# openmv2.net
KiCad netlist of a schematic drawn in EAGLE
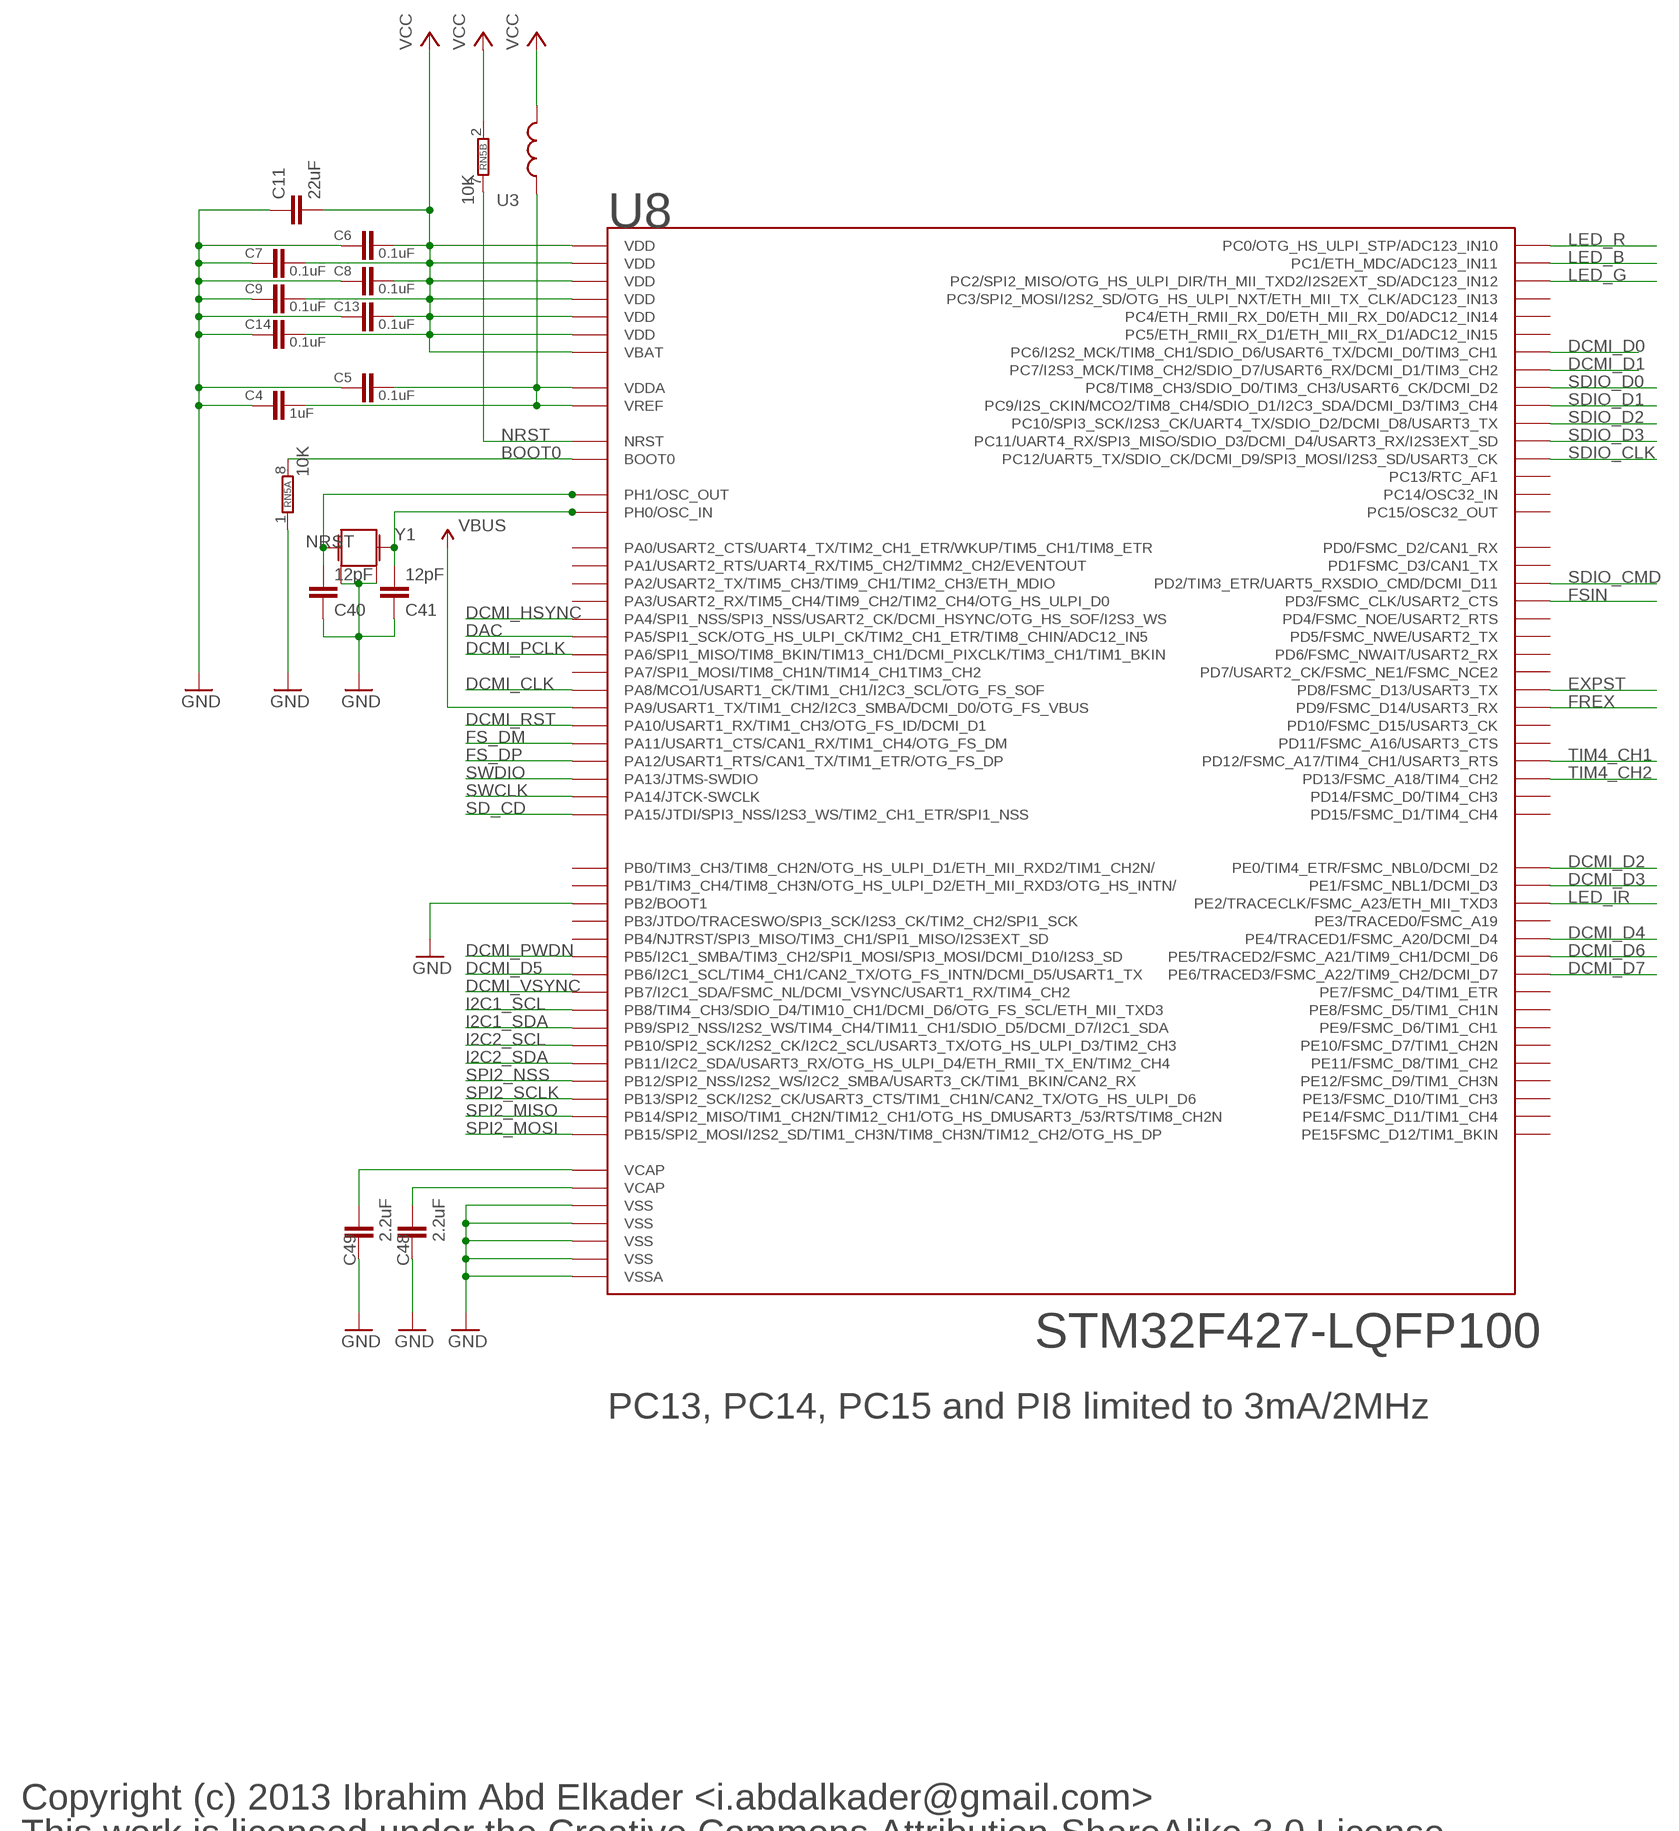
[diagram p0: schematic, sheet 1, part 1 of 2]
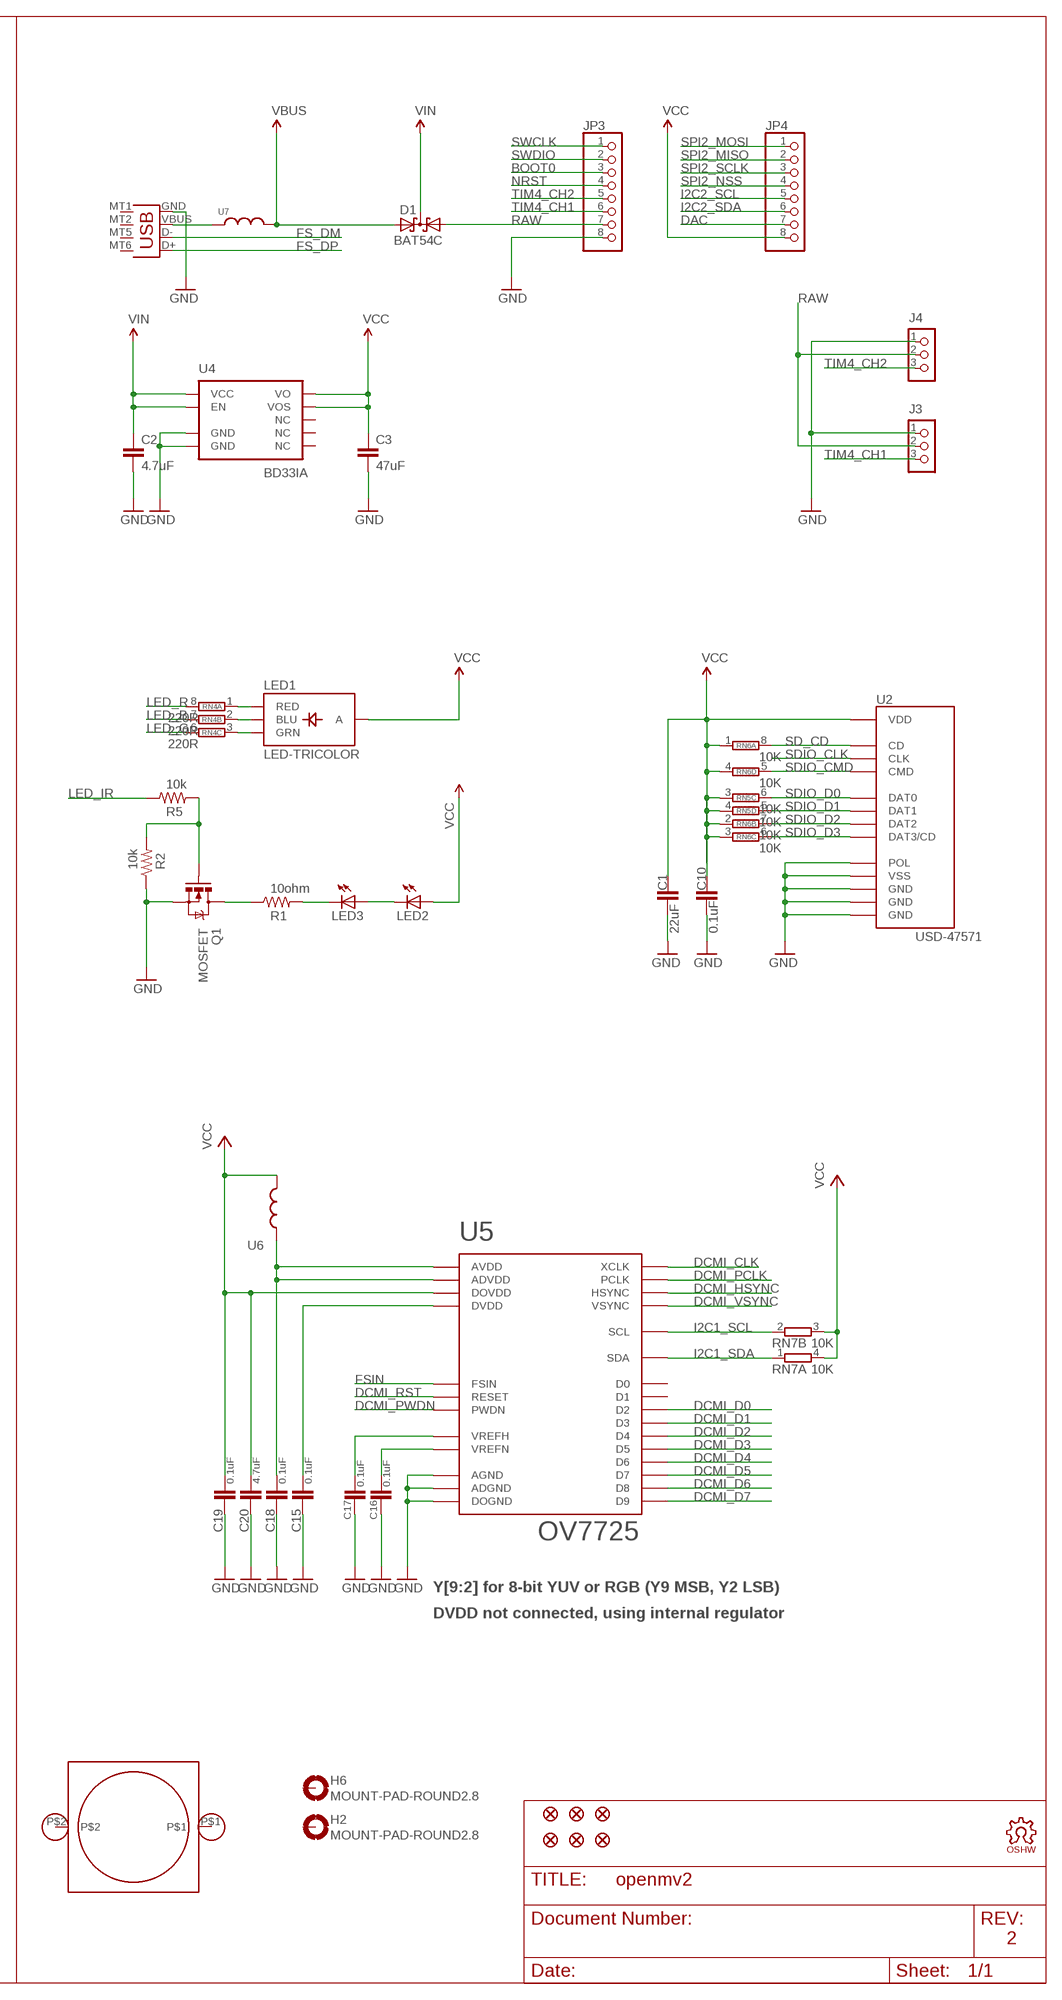
[diagram p1: schematic, sheet 1, part 2 of 2]

(export (version "E")
  (design (tool "Eeschema 10.0.6"))
  (components
    (comp (ref "C1")
      (value "22uF")
      (footprint "eagle-import:0805")
      (libsource (lib "eagle-import") (part "CAP0805"))
    )
    (comp (ref "C2")
      (value "4.7uF")
      (footprint "eagle-import:0603-CAP")
      (libsource (lib "eagle-import") (part "CAP0603-CAP"))
    )
    (comp (ref "C3")
      (value "47uF")
      (footprint "eagle-import:1206")
      (libsource (lib "eagle-import") (part "CAP1206"))
    )
    (comp (ref "C4")
      (value "1uF")
      (footprint "eagle-import:0603-CAP")
      (libsource (lib "eagle-import") (part "CAP0603-CAP"))
    )
    (comp (ref "C5")
      (value "0.1uF")
      (footprint "eagle-import:0603-CAP")
      (libsource (lib "eagle-import") (part "CAP0603-CAP"))
    )
    (comp (ref "C6")
      (value "0.1uF")
      (footprint "eagle-import:0603-CAP")
      (libsource (lib "eagle-import") (part "CAP0603-CAP"))
    )
    (comp (ref "C7")
      (value "0.1uF")
      (footprint "eagle-import:0603-CAP")
      (libsource (lib "eagle-import") (part "CAP0603-CAP"))
    )
    (comp (ref "C8")
      (value "0.1uF")
      (footprint "eagle-import:0603-CAP")
      (libsource (lib "eagle-import") (part "CAP0603-CAP"))
    )
    (comp (ref "C9")
      (value "0.1uF")
      (footprint "eagle-import:0603-CAP")
      (libsource (lib "eagle-import") (part "CAP0603-CAP"))
    )
    (comp (ref "C10")
      (value "0.1uF")
      (footprint "eagle-import:0603-CAP")
      (libsource (lib "eagle-import") (part "CAP0603-CAP"))
    )
    (comp (ref "C11")
      (value "22uF")
      (footprint "eagle-import:0805")
      (libsource (lib "eagle-import") (part "CAP0805"))
    )
    (comp (ref "C13")
      (value "0.1uF")
      (footprint "eagle-import:0603-CAP")
      (libsource (lib "eagle-import") (part "CAP0603-CAP"))
    )
    (comp (ref "C14")
      (value "0.1uF")
      (footprint "eagle-import:0603-CAP")
      (libsource (lib "eagle-import") (part "CAP0603-CAP"))
    )
    (comp (ref "C15")
      (value "0.1uF")
      (footprint "eagle-import:0603-CAP")
      (libsource (lib "eagle-import") (part "CAP0603-CAP"))
    )
    (comp (ref "C16")
      (value "0.1uF")
      (footprint "eagle-import:0603-CAP")
      (libsource (lib "eagle-import") (part "CAP0603-CAP"))
    )
    (comp (ref "C17")
      (value "0.1uF")
      (footprint "eagle-import:0603-CAP")
      (libsource (lib "eagle-import") (part "CAP0603-CAP"))
    )
    (comp (ref "C18")
      (value "0.1uF")
      (footprint "eagle-import:0603-CAP")
      (libsource (lib "eagle-import") (part "CAP0603-CAP"))
    )
    (comp (ref "C19")
      (value "0.1uF")
      (footprint "eagle-import:0603-CAP")
      (libsource (lib "eagle-import") (part "CAP0603-CAP"))
    )
    (comp (ref "C20")
      (value "4.7uF")
      (footprint "eagle-import:0603-CAP")
      (libsource (lib "eagle-import") (part "CAP0603-CAP"))
    )
    (comp (ref "C40")
      (value "12pF")
      (footprint "eagle-import:0603-CAP")
      (libsource (lib "eagle-import") (part "CAP0603-CAP"))
    )
    (comp (ref "C41")
      (value "12pF")
      (footprint "eagle-import:0603-CAP")
      (libsource (lib "eagle-import") (part "CAP0603-CAP"))
    )
    (comp (ref "C48")
      (value "2.2uF")
      (footprint "eagle-import:0603-CAP")
      (libsource (lib "eagle-import") (part "CAP0603-CAP"))
    )
    (comp (ref "C49")
      (value "2.2uF")
      (footprint "eagle-import:0603-CAP")
      (libsource (lib "eagle-import") (part "CAP0603-CAP"))
    )
    (comp (ref "D1")
      (value "BAT54C")
      (footprint "eagle-import:SOT23")
      (libsource (lib "eagle-import") (part "BAT54C"))
    )
    (comp (ref "H2")
      (value "MOUNT-PAD-ROUND2.8")
      (footprint "eagle-import:2,8-PAD")
      (libsource (lib "eagle-import") (part "MOUNT-PAD-ROUND2.8"))
    )
    (comp (ref "H6")
      (value "MOUNT-PAD-ROUND2.8")
      (footprint "eagle-import:2,8-PAD")
      (libsource (lib "eagle-import") (part "MOUNT-PAD-ROUND2.8"))
    )
    (comp (ref "J3")
      (value "CON_HEADER_1X03")
      (footprint "eagle-import:M1X3_SMD")
      (libsource (lib "eagle-import") (part "CON_HEADER_1X03"))
    )
    (comp (ref "J4")
      (value "CON_HEADER_1X03")
      (footprint "eagle-import:M1X3_SMD")
      (libsource (lib "eagle-import") (part "CON_HEADER_1X03"))
    )
    (comp (ref "JP1")
      (value "FIDUCIAL1X2")
      (footprint "eagle-import:FIDUCIAL-1X2")
      (libsource (lib "eagle-import") (part "FIDUCIAL1X2"))
    )
    (comp (ref "JP2")
      (value "FIDUCIAL1X2")
      (footprint "eagle-import:FIDUCIAL-1X2")
      (libsource (lib "eagle-import") (part "FIDUCIAL1X2"))
    )
    (comp (ref "JP3")
      (value "PINHD-1X8")
      (footprint "eagle-import:1X08")
      (libsource (lib "eagle-import") (part "PINHD-1X8"))
    )
    (comp (ref "JP4")
      (value "PINHD-1X8")
      (footprint "eagle-import:1X08")
      (libsource (lib "eagle-import") (part "PINHD-1X8"))
    )
    (comp (ref "JP5")
      (value "FIDUCIAL1X2")
      (footprint "eagle-import:FIDUCIAL-1X2")
      (libsource (lib "eagle-import") (part "FIDUCIAL1X2"))
    )
    (comp (ref "JP6")
      (value "FIDUCIAL1X2")
      (footprint "eagle-import:FIDUCIAL-1X2")
      (libsource (lib "eagle-import") (part "FIDUCIAL1X2"))
    )
    (comp (ref "JP7")
      (value "FIDUCIAL1X2")
      (footprint "eagle-import:FIDUCIAL-1X2")
      (libsource (lib "eagle-import") (part "FIDUCIAL1X2"))
    )
    (comp (ref "JP8")
      (value "FIDUCIAL1X2")
      (footprint "eagle-import:FIDUCIAL-1X2")
      (libsource (lib "eagle-import") (part "FIDUCIAL1X2"))
    )
    (comp (ref "LED1")
      (value "LED-TRICOLOR")
      (footprint "eagle-import:LED-TRICOLOR-SMD")
      (libsource (lib "eagle-import") (part "LED-TRICOLOR"))
    )
    (comp (ref "LED2")
      (value "LED3MM")
      (footprint "eagle-import:LED3MM")
      (libsource (lib "eagle-import") (part "LED3MM"))
    )
    (comp (ref "LED3")
      (value "LED3MM")
      (footprint "eagle-import:LED3MM")
      (libsource (lib "eagle-import") (part "LED3MM"))
    )
    (comp (ref "LOGO1")
      (value "OSHW_LOGO_FILLX0150-NT")
      (footprint "eagle-import:OSHW_FILLX150_NOTEXT")
      (libsource (lib "eagle-import") (part "OSHW_LOGO_FILLX0150-NT"))
    )
    (comp (ref "Q1")
      (value "MOSFET")
      (footprint "eagle-import:SOT23-3")
      (libsource (lib "eagle-import") (part "MOSFET-NCHANNELSMD"))
    )
    (comp (ref "R1")
      (value "10ohm")
      (footprint "eagle-import:0603-RES")
      (libsource (lib "eagle-import") (part "RESISTOR0603-RES"))
    )
    (comp (ref "R2")
      (value "10k")
      (footprint "eagle-import:0603-RES")
      (libsource (lib "eagle-import") (part "RESISTOR0603-RES"))
    )
    (comp (ref "R5")
      (value "10k")
      (footprint "eagle-import:0603-RES")
      (libsource (lib "eagle-import") (part "RESISTOR0603-RES"))
    )
    (comp (ref "RN4")
      (value "220R")
      (footprint "eagle-import:EXBV8V")
      (fields (field (name "OC_FARNELL") "unknown") (field (name "OC_NEWARK") "unknown"))
      (libsource (lib "eagle-import") (part "4R-NEXBV8V"))
    )
    (comp (ref "RN5")
      (value "10K")
      (footprint "eagle-import:EXBV8V")
      (fields (field (name "OC_FARNELL") "unknown") (field (name "OC_NEWARK") "unknown"))
      (libsource (lib "eagle-import") (part "4R-NEXBV8V"))
    )
    (comp (ref "RN6")
      (value "10K")
      (footprint "eagle-import:EXBV8V")
      (fields (field (name "OC_FARNELL") "unknown") (field (name "OC_NEWARK") "unknown"))
      (libsource (lib "eagle-import") (part "4R-NEXBV8V"))
    )
    (comp (ref "RN7")
      (value "10K")
      (footprint "eagle-import:EXBV4V")
      (libsource (lib "eagle-import") (part "2R-NEXBV4V"))
    )
    (comp (ref "U1")
      (value "LENSMOUNT20MM")
      (footprint "eagle-import:LENSMOUNT-20MM")
      (libsource (lib "eagle-import") (part "LENSMOUNT20MM"))
    )
    (comp (ref "U2")
      (value "USD-47571")
      (footprint "eagle-import:USD-47571")
      (libsource (lib "eagle-import") (part "USD-47571"))
    )
    (comp (ref "U3")
      (value "INDUCTOR0603")
      (footprint "eagle-import:0603")
      (libsource (lib "eagle-import") (part "INDUCTOR0603"))
    )
    (comp (ref "U4")
      (value "BD33IA")
      (footprint "eagle-import:HTSOP-J8")
      (libsource (lib "eagle-import") (part "BD33IA"))
    )
    (comp (ref "U5")
      (value "OV7725")
      (footprint "eagle-import:CSP2-28")
      (libsource (lib "eagle-import") (part "OV7725"))
    )
    (comp (ref "U6")
      (value "INDUCTOR0603")
      (footprint "eagle-import:0603")
      (libsource (lib "eagle-import") (part "INDUCTOR0603"))
    )
    (comp (ref "U7")
      (value "INDUCTOR0603")
      (footprint "eagle-import:0603")
      (libsource (lib "eagle-import") (part "INDUCTOR0603"))
    )
    (comp (ref "U8")
      (value "STM32F427-LQFP100")
      (footprint "eagle-import:LQFP100")
      (libsource (lib "eagle-import") (part "STM32F407LQFP100"))
    )
    (comp (ref "X2")
      (value "USB-MICROB")
      (footprint "eagle-import:USB-MICROB")
      (libsource (lib "eagle-import") (part "USB-MICROB"))
    )
    (comp (ref "Y1")
      (value "CRYSTAL2.5X2.0")
      (footprint "eagle-import:CRYSTAL-2.5X2.0")
      (libsource (lib "eagle-import") (part "CRYSTAL2.5X2.0"))
    )
  )
  (nets
    (net (code "1") (name "/BOOT0") (class "Default")
      (node (ref "JP3") (pin "3") (pinfunction "3_3") (pintype "passive"))
      (node (ref "RN5") (pin "8") (pinfunction "2_8") (pintype "passive"))
      (node (ref "U8") (pin "94") (pinfunction "BOOT0_94") (pintype "bidirectional"))
    )
    (net (code "2") (name "/DAC") (class "Default")
      (node (ref "JP4") (pin "7") (pinfunction "7_7") (pintype "passive"))
      (node (ref "U8") (pin "30") (pinfunction "PA5/SPI1_SCK/OTG_HS_ULPI_CK/TIM2_CH1_ETR/TIM8_CHIN/ADC12_IN5_30") (pintype "bidirectional"))
    )
    (net (code "3") (name "/DCMI_CLK") (class "Default")
      (node (ref "U5") (pin "F3") (pinfunction "XCLK_F3") (pintype "bidirectional"))
      (node (ref "U8") (pin "67") (pinfunction "PA8/MCO1/USART1_CK/TIM1_CH1/I2C3_SCL/OTG_FS_SOF_67") (pintype "bidirectional"))
    )
    (net (code "4") (name "/DCMI_D0") (class "Default")
      (node (ref "U5") (pin "F5") (pinfunction "D2_F5") (pintype "bidirectional"))
      (node (ref "U8") (pin "63") (pinfunction "PC6/I2S2_MCK/TIM8_CH1/SDIO_D6/USART6_TX/DCMI_D0/TIM3_CH1_63") (pintype "bidirectional"))
    )
    (net (code "5") (name "/DCMI_D1") (class "Default")
      (node (ref "U5") (pin "F2") (pinfunction "D3_F2") (pintype "bidirectional"))
      (node (ref "U8") (pin "64") (pinfunction "PC7/I2S3_MCK/TIM8_CH2/SDIO_D7/USART6_RX/DCMI_D1/TIM3_CH2_64") (pintype "bidirectional"))
    )
    (net (code "6") (name "/DCMI_D2") (class "Default")
      (node (ref "U5") (pin "D6") (pinfunction "D4_D6") (pintype "bidirectional"))
      (node (ref "U8") (pin "97") (pinfunction "PE0/TIM4_ETR/FSMC_NBL0/DCMI_D2_97") (pintype "bidirectional"))
    )
    (net (code "7") (name "/DCMI_D3") (class "Default")
      (node (ref "U5") (pin "D1") (pinfunction "D5_D1") (pintype "bidirectional"))
      (node (ref "U8") (pin "98") (pinfunction "PE1/FSMC_NBL1/DCMI_D3_98") (pintype "bidirectional"))
    )
    (net (code "8") (name "/DCMI_D4") (class "Default")
      (node (ref "U5") (pin "E6") (pinfunction "D6_E6") (pintype "bidirectional"))
      (node (ref "U8") (pin "3") (pinfunction "PE4/TRACED1/FSMC_A20/DCMI_D4_3") (pintype "bidirectional"))
    )
    (net (code "9") (name "/DCMI_D5") (class "Default")
      (node (ref "U5") (pin "E1") (pinfunction "D7_E1") (pintype "bidirectional"))
      (node (ref "U8") (pin "92") (pinfunction "PB6/I2C1_SCL/TIM4_CH1/CAN2_TX/OTG_FS_INTN/DCMI_D5/USART1_TX_92") (pintype "bidirectional"))
    )
    (net (code "10") (name "/DCMI_D6") (class "Default")
      (node (ref "U5") (pin "F6") (pinfunction "D8_F6") (pintype "bidirectional"))
      (node (ref "U8") (pin "4") (pinfunction "PE5/TRACED2/FSMC_A21/TIM9_CH1/DCMI_D6_4") (pintype "bidirectional"))
    )
    (net (code "11") (name "/DCMI_D7") (class "Default")
      (node (ref "U5") (pin "F1") (pinfunction "D9_F1") (pintype "bidirectional"))
      (node (ref "U8") (pin "5") (pinfunction "PE6/TRACED3/FSMC_A22/TIM9_CH2/DCMI_D7_5") (pintype "bidirectional"))
    )
    (net (code "12") (name "/DCMI_HSYNC") (class "Default")
      (node (ref "U5") (pin "B6") (pinfunction "HSYNC_B6") (pintype "bidirectional"))
      (node (ref "U8") (pin "29") (pinfunction "PA4/SPI1_NSS/SPI3_NSS/USART2_CK/DCMI_HSYNC/OTG_HS_SOF/I2S3_WS_29") (pintype "bidirectional"))
    )
    (net (code "13") (name "/DCMI_PCLK") (class "Default")
      (node (ref "U5") (pin "E4") (pinfunction "PCLK_E4") (pintype "bidirectional"))
      (node (ref "U8") (pin "31") (pinfunction "PA6/SPI1_MISO/TIM8_BKIN/TIM13_CH1/DCMI_PIXCLK/TIM3_CH1/TIM1_BKIN_31") (pintype "bidirectional"))
    )
    (net (code "14") (name "/DCMI_PWDN") (class "Default")
      (node (ref "U5") (pin "C1") (pinfunction "PWDN_C1") (pintype "bidirectional"))
      (node (ref "U8") (pin "91") (pinfunction "PB5/I2C1_SMBA/TIM3_CH2/SPI1_MOSI/SPI3_MOSI/DCMI_D10/I2S3_SD_91") (pintype "bidirectional"))
    )
    (net (code "15") (name "/DCMI_RST") (class "Default")
      (node (ref "U5") (pin "A2") (pinfunction "RESET_A2") (pintype "bidirectional"))
      (node (ref "U8") (pin "69") (pinfunction "PA10/USART1_RX/TIM1_CH3/OTG_FS_ID/DCMI_D1_69") (pintype "bidirectional"))
    )
    (net (code "16") (name "/DCMI_VSYNC") (class "Default")
      (node (ref "U5") (pin "C6") (pinfunction "VSYNC_C6") (pintype "bidirectional"))
      (node (ref "U8") (pin "93") (pinfunction "PB7/I2C1_SDA/FSMC_NL/DCMI_VSYNC/USART1_RX/TIM4_CH2_93") (pintype "bidirectional"))
    )
    (net (code "17") (name "/EXPST") (class "Default")
      (node (ref "U8") (pin "55") (pinfunction "PD8/FSMC_D13/USART3_TX_55") (pintype "bidirectional"))
    )
    (net (code "18") (name "/FREX") (class "Default")
      (node (ref "U8") (pin "56") (pinfunction "PD9/FSMC_D14/USART3_RX_56") (pintype "bidirectional"))
    )
    (net (code "19") (name "/FSIN") (class "Default")
      (node (ref "U5") (pin "A4") (pinfunction "FSIN_A4") (pintype "input"))
      (node (ref "U8") (pin "84") (pinfunction "PD3/FSMC_CLK/USART2_CTS_84") (pintype "bidirectional"))
    )
    (net (code "20") (name "/FS_DM") (class "Default")
      (node (ref "U8") (pin "70") (pinfunction "PA11/USART1_CTS/CAN1_RX/TIM1_CH4/OTG_FS_DM_70") (pintype "bidirectional"))
      (node (ref "X2") (pin "D-") (pinfunction "D-_D-") (pintype "bidirectional"))
    )
    (net (code "21") (name "/FS_DP") (class "Default")
      (node (ref "U8") (pin "71") (pinfunction "PA12/USART1_RTS/CAN1_TX/TIM1_ETR/OTG_FS_DP_71") (pintype "bidirectional"))
      (node (ref "X2") (pin "D+") (pinfunction "D+_D+") (pintype "bidirectional"))
    )
    (net (code "22") (name "/I2C1_SCL") (class "Default")
      (node (ref "RN7") (pin "2") (pinfunction "1_2") (pintype "passive"))
      (node (ref "U5") (pin "A5") (pinfunction "SCL_A5") (pintype "bidirectional"))
      (node (ref "U8") (pin "95") (pinfunction "PB8/TIM4_CH3/SDIO_D4/TIM10_CH1/DCMI_D6/OTG_FS_SCL/ETH_MII_TXD3_95") (pintype "bidirectional"))
    )
    (net (code "23") (name "/I2C1_SDA") (class "Default")
      (node (ref "RN7") (pin "1") (pinfunction "1_1") (pintype "passive"))
      (node (ref "U5") (pin "B5") (pinfunction "SDA_B5") (pintype "bidirectional"))
      (node (ref "U8") (pin "96") (pinfunction "PB9/SPI2_NSS/I2S2_WS/TIM4_CH4/TIM11_CH1/SDIO_D5/DCMI_D7/I2C1_SDA_96") (pintype "bidirectional"))
    )
    (net (code "24") (name "/I2C2_SCL") (class "Default")
      (node (ref "JP4") (pin "5") (pinfunction "5_5") (pintype "passive"))
      (node (ref "U8") (pin "47") (pinfunction "PB10/SPI2_SCK/I2S2_CK/I2C2_SCL/USART3_TX/OTG_HS_ULPI_D3/TIM2_CH3_47") (pintype "bidirectional"))
    )
    (net (code "25") (name "/I2C2_SDA") (class "Default")
      (node (ref "JP4") (pin "6") (pinfunction "6_6") (pintype "passive"))
      (node (ref "U8") (pin "48") (pinfunction "PB11/I2C2_SDA/USART3_RX/OTG_HS_ULPI_D4/ETH_RMII_TX_EN/TIM2_CH4_48") (pintype "bidirectional"))
    )
    (net (code "26") (name "/LED_B") (class "Default")
      (node (ref "RN4") (pin "7") (pinfunction "2_7") (pintype "passive"))
      (node (ref "U8") (pin "16") (pinfunction "PC1/ETH_MDC/ADC123_IN11_16") (pintype "bidirectional"))
    )
    (net (code "27") (name "/LED_G") (class "Default")
      (node (ref "RN4") (pin "6") (pinfunction "2_6") (pintype "passive"))
      (node (ref "U8") (pin "17") (pinfunction "PC2/SPI2_MISO/OTG_HS_ULPI_DIR/TH_MII_TXD2/I2S2EXT_SD/ADC123_IN12_17") (pintype "bidirectional"))
    )
    (net (code "28") (name "/LED_IR") (class "Default")
      (node (ref "R5") (pin "1") (pinfunction "1_1") (pintype "passive"))
      (node (ref "U8") (pin "1") (pinfunction "PE2/TRACECLK/FSMC_A23/ETH_MII_TXD3_1") (pintype "bidirectional"))
    )
    (net (code "29") (name "/LED_R") (class "Default")
      (node (ref "RN4") (pin "8") (pinfunction "2_8") (pintype "passive"))
      (node (ref "U8") (pin "15") (pinfunction "PC0/OTG_HS_ULPI_STP/ADC123_IN10_15") (pintype "bidirectional"))
    )
    (net (code "30") (name "/NRST") (class "Default")
      (node (ref "JP3") (pin "4") (pinfunction "4_4") (pintype "passive"))
      (node (ref "RN5") (pin "7") (pinfunction "2_7") (pintype "passive"))
      (node (ref "U8") (pin "14") (pinfunction "NRST_14") (pintype "bidirectional"))
    )
    (net (code "31") (name "/P$1") (class "Default")
      (node (ref "U1") (pin "P$1") (pinfunction "P$1_P$1") (pintype "power_in"))
    )
    (net (code "32") (name "/P$2") (class "Default")
      (node (ref "U1") (pin "P$2") (pinfunction "P$2_P$2") (pintype "power_in"))
    )
    (net (code "33") (name "/RAW") (class "Default")
      (node (ref "D1") (pin "1") (pinfunction "A1_1") (pintype "passive"))
      (node (ref "J3") (pin "2") (pinfunction "2_2") (pintype "bidirectional"))
      (node (ref "J4") (pin "2") (pinfunction "2_2") (pintype "bidirectional"))
      (node (ref "JP3") (pin "7") (pinfunction "7_7") (pintype "passive"))
    )
    (net (code "34") (name "/SDIO_CLK") (class "Default")
      (node (ref "U2") (pin "P$5") (pinfunction "CLK_P$5") (pintype "bidirectional"))
      (node (ref "U8") (pin "80") (pinfunction "PC12/UART5_TX/SDIO_CK/DCMI_D9/SPI3_MOSI/I2S3_SD/USART3_CK_80") (pintype "bidirectional"))
    )
    (net (code "35") (name "/SDIO_CMD") (class "Default")
      (node (ref "RN6") (pin "5") (pinfunction "2_5") (pintype "passive"))
      (node (ref "U2") (pin "P$3") (pinfunction "CMD_P$3") (pintype "bidirectional"))
      (node (ref "U8") (pin "83") (pinfunction "PD2/TIM3_ETR/UART5_RXSDIO_CMD/DCMI_D11_83") (pintype "bidirectional"))
    )
    (net (code "36") (name "/SDIO_D0") (class "Default")
      (node (ref "RN5") (pin "6") (pinfunction "2_6") (pintype "passive"))
      (node (ref "U2") (pin "P$7") (pinfunction "DAT0_P$7") (pintype "bidirectional"))
      (node (ref "U8") (pin "65") (pinfunction "PC8/TIM8_CH3/SDIO_D0/TIM3_CH3/USART6_CK/DCMI_D2_65") (pintype "bidirectional"))
    )
    (net (code "37") (name "/SDIO_D1") (class "Default")
      (node (ref "RN5") (pin "5") (pinfunction "2_5") (pintype "passive"))
      (node (ref "U2") (pin "P$8") (pinfunction "DAT1_P$8") (pintype "bidirectional"))
      (node (ref "U8") (pin "66") (pinfunction "PC9/I2S_CKIN/MCO2/TIM8_CH4/SDIO_D1/I2C3_SDA/DCMI_D3/TIM3_CH4_66") (pintype "bidirectional"))
    )
    (net (code "38") (name "/SDIO_D2") (class "Default")
      (node (ref "RN6") (pin "7") (pinfunction "2_7") (pintype "passive"))
      (node (ref "U2") (pin "P$1") (pinfunction "DAT2_P$1") (pintype "bidirectional"))
      (node (ref "U8") (pin "78") (pinfunction "PC10/SPI3_SCK/I2S3_CK/UART4_TX/SDIO_D2/DCMI_D8/USART3_TX_78") (pintype "bidirectional"))
    )
    (net (code "39") (name "/SDIO_D3") (class "Default")
      (node (ref "RN6") (pin "6") (pinfunction "2_6") (pintype "passive"))
      (node (ref "U2") (pin "P$2") (pinfunction "DAT3/CD_P$2") (pintype "bidirectional"))
      (node (ref "U8") (pin "79") (pinfunction "PC11/UART4_RX/SPI3_MISO/SDIO_D3/DCMI_D4/USART3_RX/I2S3EXT_SD_79") (pintype "bidirectional"))
    )
    (net (code "40") (name "/SD_CD") (class "Default")
      (node (ref "RN6") (pin "8") (pinfunction "2_8") (pintype "passive"))
      (node (ref "U2") (pin "G$5") (pinfunction "CD_G$5") (pintype "power_in"))
      (node (ref "U8") (pin "77") (pinfunction "PA15/JTDI/SPI3_NSS/I2S3_WS/TIM2_CH1_ETR/SPI1_NSS_77") (pintype "bidirectional"))
    )
    (net (code "41") (name "/SPI2_MISO") (class "Default")
      (node (ref "JP4") (pin "2") (pinfunction "2_2") (pintype "passive"))
      (node (ref "U8") (pin "53") (pinfunction "PB14/SPI2_MISO/TIM1_CH2N/TIM12_CH1/OTG_HS_DMUSART3_/53/RTS/TIM8_CH2N_53") (pintype "bidirectional"))
    )
    (net (code "42") (name "/SPI2_MOSI") (class "Default")
      (node (ref "JP4") (pin "1") (pinfunction "1_1") (pintype "passive"))
      (node (ref "U8") (pin "54") (pinfunction "PB15/SPI2_MOSI/I2S2_SD/TIM1_CH3N/TIM8_CH3N/TIM12_CH2/OTG_HS_DP_54") (pintype "bidirectional"))
    )
    (net (code "43") (name "/SPI2_NSS") (class "Default")
      (node (ref "JP4") (pin "4") (pinfunction "4_4") (pintype "passive"))
      (node (ref "U8") (pin "51") (pinfunction "PB12/SPI2_NSS/I2S2_WS/I2C2_SMBA/USART3_CK/TIM1_BKIN/CAN2_RX_51") (pintype "bidirectional"))
    )
    (net (code "44") (name "/SPI2_SCLK") (class "Default")
      (node (ref "JP4") (pin "3") (pinfunction "3_3") (pintype "passive"))
      (node (ref "U8") (pin "52") (pinfunction "PB13/SPI2_SCK/I2S2_CK/USART3_CTS/TIM1_CH1N/CAN2_TX/OTG_HS_ULPI_D6_52") (pintype "bidirectional"))
    )
    (net (code "45") (name "/SWCLK") (class "Default")
      (node (ref "JP3") (pin "1") (pinfunction "1_1") (pintype "passive"))
      (node (ref "U8") (pin "76") (pinfunction "PA14/JTCK-SWCLK_76") (pintype "bidirectional"))
    )
    (net (code "46") (name "/SWDIO") (class "Default")
      (node (ref "JP3") (pin "2") (pinfunction "2_2") (pintype "passive"))
      (node (ref "U8") (pin "72") (pinfunction "PA13/JTMS-SWDIO_72") (pintype "bidirectional"))
    )
    (net (code "47") (name "/TIM4_CH1") (class "Default")
      (node (ref "J3") (pin "3") (pinfunction "3_3") (pintype "bidirectional"))
      (node (ref "JP3") (pin "6") (pinfunction "6_6") (pintype "passive"))
      (node (ref "U8") (pin "59") (pinfunction "PD12/FSMC_A17/TIM4_CH1/USART3_RTS_59") (pintype "bidirectional"))
    )
    (net (code "48") (name "/TIM4_CH2") (class "Default")
      (node (ref "J4") (pin "3") (pinfunction "3_3") (pintype "bidirectional"))
      (node (ref "JP3") (pin "5") (pinfunction "5_5") (pintype "passive"))
      (node (ref "U8") (pin "60") (pinfunction "PD13/FSMC_A18/TIM4_CH2_60") (pintype "bidirectional"))
    )
    (net (code "49") (name "GND") (class "Default")
      (node (ref "C1") (pin "2") (pinfunction "2_2") (pintype "passive"))
      (node (ref "C10") (pin "2") (pinfunction "2_2") (pintype "passive"))
      (node (ref "C11") (pin "1") (pinfunction "1_1") (pintype "passive"))
      (node (ref "C13") (pin "2") (pinfunction "2_2") (pintype "passive"))
      (node (ref "C14") (pin "2") (pinfunction "2_2") (pintype "passive"))
      (node (ref "C15") (pin "2") (pinfunction "2_2") (pintype "passive"))
      (node (ref "C16") (pin "2") (pinfunction "2_2") (pintype "passive"))
      (node (ref "C17") (pin "2") (pinfunction "2_2") (pintype "passive"))
      (node (ref "C18") (pin "2") (pinfunction "2_2") (pintype "passive"))
      (node (ref "C19") (pin "2") (pinfunction "2_2") (pintype "passive"))
      (node (ref "C2") (pin "2") (pinfunction "2_2") (pintype "passive"))
      (node (ref "C20") (pin "2") (pinfunction "2_2") (pintype "passive"))
      (node (ref "C3") (pin "2") (pinfunction "2_2") (pintype "passive"))
      (node (ref "C4") (pin "2") (pinfunction "2_2") (pintype "passive"))
      (node (ref "C40") (pin "1") (pinfunction "1_1") (pintype "passive"))
      (node (ref "C41") (pin "1") (pinfunction "1_1") (pintype "passive"))
      (node (ref "C48") (pin "2") (pinfunction "2_2") (pintype "passive"))
      (node (ref "C49") (pin "2") (pinfunction "2_2") (pintype "passive"))
      (node (ref "C5") (pin "2") (pinfunction "2_2") (pintype "passive"))
      (node (ref "C6") (pin "2") (pinfunction "2_2") (pintype "passive"))
      (node (ref "C7") (pin "2") (pinfunction "2_2") (pintype "passive"))
      (node (ref "C8") (pin "2") (pinfunction "2_2") (pintype "passive"))
      (node (ref "C9") (pin "2") (pinfunction "2_2") (pintype "passive"))
      (node (ref "J3") (pin "1") (pinfunction "1_1") (pintype "bidirectional"))
      (node (ref "J4") (pin "1") (pinfunction "1_1") (pintype "bidirectional"))
      (node (ref "JP3") (pin "8") (pinfunction "8_8") (pintype "passive"))
      (node (ref "Q1") (pin "2") (pinfunction "S_2") (pintype "passive"))
      (node (ref "R2") (pin "1") (pinfunction "1_1") (pintype "passive"))
      (node (ref "RN5") (pin "1") (pinfunction "1_1") (pintype "passive"))
      (node (ref "U2") (pin "G$1") (pinfunction "GND_G$1") (pintype "power_in"))
      (node (ref "U2") (pin "G$2") (pinfunction "GND_G$2") (pintype "power_in"))
      (node (ref "U2") (pin "G$3") (pinfunction "GND_G$3") (pintype "power_in"))
      (node (ref "U2") (pin "G$4") (pinfunction "POL_G$4") (pintype "power_in"))
      (node (ref "U2") (pin "P$6") (pinfunction "VSS_P$6") (pintype "power_in"))
      (node (ref "U4") (pin "3") (pinfunction "GND_3") (pintype "input"))
      (node (ref "U4") (pin "P$1") (pinfunction "GND_P$1") (pintype "input"))
      (node (ref "U5") (pin "B1") (pinfunction "ADGND_B1") (pintype "power_in"))
      (node (ref "U5") (pin "B4") (pinfunction "AGND_B4") (pintype "power_in"))
      (node (ref "U5") (pin "F4") (pinfunction "DOGND_F4") (pintype "power_in"))
      (node (ref "U8") (pin "10") (pinfunction "VSS_10") (pintype "power_in"))
      (node (ref "U8") (pin "20") (pinfunction "VSSA_20") (pintype "power_in"))
      (node (ref "U8") (pin "27") (pinfunction "VSS_27") (pintype "power_in"))
      (node (ref "U8") (pin "37") (pinfunction "PB2/BOOT1_37") (pintype "bidirectional"))
      (node (ref "U8") (pin "74") (pinfunction "VSS_74") (pintype "power_in"))
      (node (ref "U8") (pin "99") (pinfunction "VSS_99") (pintype "power_in"))
      (node (ref "X2") (pin "GND") (pinfunction "GND_GND") (pintype "bidirectional"))
      (node (ref "Y1") (pin "2") (pinfunction "P$1_2") (pintype "power_in"))
      (node (ref "Y1") (pin "4") (pinfunction "P$2_4") (pintype "power_in"))
    )
    (net (code "50") (name "Net-(C48-Pad1)") (class "Default")
      (node (ref "C48") (pin "1") (pinfunction "1_1") (pintype "passive"))
      (node (ref "U8") (pin "73") (pinfunction "VCAP_73") (pintype "power_in"))
    )
    (net (code "51") (name "Net-(C49-Pad1)") (class "Default")
      (node (ref "C49") (pin "1") (pinfunction "1_1") (pintype "passive"))
      (node (ref "U8") (pin "49") (pinfunction "VCAP_49") (pintype "power_in"))
    )
    (net (code "52") (name "Net-(LED1-BLU)") (class "Default")
      (node (ref "LED1") (pin "B") (pinfunction "BLU_B") (pintype "bidirectional"))
      (node (ref "RN4") (pin "2") (pinfunction "1_2") (pintype "passive"))
    )
    (net (code "53") (name "Net-(LED1-GRN)") (class "Default")
      (node (ref "LED1") (pin "G") (pinfunction "GRN_G") (pintype "bidirectional"))
      (node (ref "RN4") (pin "3") (pinfunction "1_3") (pintype "passive"))
    )
    (net (code "54") (name "Net-(LED1-RED)") (class "Default")
      (node (ref "LED1") (pin "R") (pinfunction "RED_R") (pintype "bidirectional"))
      (node (ref "RN4") (pin "1") (pinfunction "1_1") (pintype "passive"))
    )
    (net (code "55") (name "Net-(LED2-C)") (class "Default")
      (node (ref "LED2") (pin "K") (pinfunction "C_K") (pintype "passive"))
      (node (ref "LED3") (pin "A") (pinfunction "A_A") (pintype "passive"))
    )
    (net (code "56") (name "Net-(LED3-C)") (class "Default")
      (node (ref "LED3") (pin "K") (pinfunction "C_K") (pintype "passive"))
      (node (ref "R1") (pin "2") (pinfunction "2_2") (pintype "passive"))
    )
    (net (code "57") (name "Net-(Q1-D)") (class "Default")
      (node (ref "Q1") (pin "3") (pinfunction "D_3") (pintype "passive"))
      (node (ref "R1") (pin "1") (pinfunction "1_1") (pintype "passive"))
    )
    (net (code "58") (name "Net-(Q1-G)") (class "Default")
      (node (ref "Q1") (pin "1") (pinfunction "G_1") (pintype "passive"))
      (node (ref "R2") (pin "2") (pinfunction "2_2") (pintype "passive"))
      (node (ref "R5") (pin "2") (pinfunction "2_2") (pintype "passive"))
    )
    (net (code "59") (name "Net-(U5-ADVDD)") (class "Default")
      (node (ref "C18") (pin "1") (pinfunction "1_1") (pintype "passive"))
      (node (ref "U5") (pin "A1") (pinfunction "ADVDD_A1") (pintype "power_in"))
      (node (ref "U5") (pin "B3") (pinfunction "AVDD_B3") (pintype "power_in"))
      (node (ref "U6") (pin "1") (pinfunction "1_1") (pintype "passive"))
    )
    (net (code "60") (name "Net-(U5-DVDD)") (class "Default")
      (node (ref "C15") (pin "1") (pinfunction "1_1") (pintype "passive"))
      (node (ref "U5") (pin "E3") (pinfunction "DVDD_E3") (pintype "power_in"))
    )
    (net (code "61") (name "Net-(U5-VREFH)") (class "Default")
      (node (ref "C17") (pin "1") (pinfunction "1_1") (pintype "passive"))
      (node (ref "U5") (pin "A3") (pinfunction "VREFH_A3") (pintype "power_in"))
    )
    (net (code "62") (name "Net-(U5-VREFN)") (class "Default")
      (node (ref "C16") (pin "1") (pinfunction "1_1") (pintype "passive"))
      (node (ref "U5") (pin "B2") (pinfunction "VREFN_B2") (pintype "power_in"))
    )
    (net (code "63") (name "Net-(U7-Pad1)") (class "Default")
      (node (ref "U7") (pin "1") (pinfunction "1_1") (pintype "passive"))
      (node (ref "X2") (pin "VBUS") (pinfunction "VBUS_VBUS") (pintype "bidirectional"))
    )
    (net (code "64") (name "Net-(U8-PH0{slash}OSC_IN)") (class "Default")
      (node (ref "C41") (pin "2") (pinfunction "2_2") (pintype "passive"))
      (node (ref "U8") (pin "12") (pinfunction "PH0/OSC_IN_12") (pintype "bidirectional"))
      (node (ref "Y1") (pin "1") (pinfunction "1_1") (pintype "passive"))
    )
    (net (code "65") (name "Net-(U8-PH1{slash}OSC_OUT)") (class "Default")
      (node (ref "C40") (pin "2") (pinfunction "2_2") (pintype "passive"))
      (node (ref "U8") (pin "13") (pinfunction "PH1/OSC_OUT_13") (pintype "bidirectional"))
      (node (ref "Y1") (pin "3") (pinfunction "2_3") (pintype "passive"))
    )
    (net (code "66") (name "Net-(U8-VDDA)") (class "Default")
      (node (ref "C4") (pin "1") (pinfunction "1_1") (pintype "passive"))
      (node (ref "C5") (pin "1") (pinfunction "1_1") (pintype "passive"))
      (node (ref "U3") (pin "1") (pinfunction "1_1") (pintype "passive"))
      (node (ref "U8") (pin "21") (pinfunction "VREF_21") (pintype "power_in"))
      (node (ref "U8") (pin "22") (pinfunction "VDDA_22") (pintype "power_in"))
    )
    (net (code "67") (name "VBUS") (class "Default")
      (node (ref "D1") (pin "2") (pinfunction "A2_2") (pintype "passive"))
      (node (ref "U7") (pin "2") (pinfunction "2_2") (pintype "passive"))
      (node (ref "U8") (pin "68") (pinfunction "PA9/USART1_TX/TIM1_CH2/I2C3_SMBA/DCMI_D0/OTG_FS_VBUS_68") (pintype "bidirectional"))
    )
    (net (code "68") (name "VCC") (class "Default")
      (node (ref "C1") (pin "1") (pinfunction "1_1") (pintype "passive"))
      (node (ref "C10") (pin "1") (pinfunction "1_1") (pintype "passive"))
      (node (ref "C11") (pin "2") (pinfunction "2_2") (pintype "passive"))
      (node (ref "C13") (pin "1") (pinfunction "1_1") (pintype "passive"))
      (node (ref "C14") (pin "1") (pinfunction "1_1") (pintype "passive"))
      (node (ref "C19") (pin "1") (pinfunction "1_1") (pintype "passive"))
      (node (ref "C20") (pin "1") (pinfunction "1_1") (pintype "passive"))
      (node (ref "C3") (pin "1") (pinfunction "1_1") (pintype "passive"))
      (node (ref "C6") (pin "1") (pinfunction "1_1") (pintype "passive"))
      (node (ref "C7") (pin "1") (pinfunction "1_1") (pintype "passive"))
      (node (ref "C8") (pin "1") (pinfunction "1_1") (pintype "passive"))
      (node (ref "C9") (pin "1") (pinfunction "1_1") (pintype "passive"))
      (node (ref "JP4") (pin "8") (pinfunction "8_8") (pintype "passive"))
      (node (ref "LED1") (pin "A") (pinfunction "A_A") (pintype "bidirectional"))
      (node (ref "LED2") (pin "A") (pinfunction "A_A") (pintype "passive"))
      (node (ref "RN5") (pin "2") (pinfunction "1_2") (pintype "passive"))
      (node (ref "RN5") (pin "3") (pinfunction "1_3") (pintype "passive"))
      (node (ref "RN5") (pin "4") (pinfunction "1_4") (pintype "passive"))
      (node (ref "RN6") (pin "1") (pinfunction "1_1") (pintype "passive"))
      (node (ref "RN6") (pin "2") (pinfunction "1_2") (pintype "passive"))
      (node (ref "RN6") (pin "3") (pinfunction "1_3") (pintype "passive"))
      (node (ref "RN6") (pin "4") (pinfunction "1_4") (pintype "passive"))
      (node (ref "RN7") (pin "3") (pinfunction "2_3") (pintype "passive"))
      (node (ref "RN7") (pin "4") (pinfunction "2_4") (pintype "passive"))
      (node (ref "U2") (pin "P$4") (pinfunction "VDD_P$4") (pintype "power_in"))
      (node (ref "U3") (pin "2") (pinfunction "2_2") (pintype "passive"))
      (node (ref "U4") (pin "1") (pinfunction "VO_1") (pintype "output"))
      (node (ref "U4") (pin "2") (pinfunction "VOS_2") (pintype "output"))
      (node (ref "U5") (pin "E5") (pinfunction "DOVDD_E5") (pintype "power_in"))
      (node (ref "U6") (pin "2") (pinfunction "2_2") (pintype "passive"))
      (node (ref "U8") (pin "100") (pinfunction "VDD_100") (pintype "power_in"))
      (node (ref "U8") (pin "11") (pinfunction "VDD_11") (pintype "power_in"))
      (node (ref "U8") (pin "19") (pinfunction "VDD_19") (pintype "power_in"))
      (node (ref "U8") (pin "28") (pinfunction "VDD_28") (pintype "power_in"))
      (node (ref "U8") (pin "50") (pinfunction "VDD_50") (pintype "power_in"))
      (node (ref "U8") (pin "6") (pinfunction "VBAT_6") (pintype "power_in"))
      (node (ref "U8") (pin "75") (pinfunction "VDD_75") (pintype "power_in"))
    )
    (net (code "69") (name "VIN") (class "Default")
      (node (ref "C2") (pin "1") (pinfunction "1_1") (pintype "passive"))
      (node (ref "D1") (pin "3") (pinfunction "CC_3") (pintype "passive"))
      (node (ref "U4") (pin "5") (pinfunction "EN_5") (pintype "input"))
      (node (ref "U4") (pin "8") (pinfunction "VCC_8") (pintype "input"))
    )
    (net (code "70") (name "unconnected-(H2-MOUNT-PadB2,8)") (class "Default")
      (node (ref "H2") (pin "B2,8") (pinfunction "MOUNT_B2,8") (pintype "passive"))
    )
    (net (code "71") (name "unconnected-(H6-MOUNT-PadB2,8)") (class "Default")
      (node (ref "H6") (pin "B2,8") (pinfunction "MOUNT_B2,8") (pintype "passive"))
    )
    (net (code "72") (name "unconnected-(U4-NC-Pad4)") (class "Default")
      (node (ref "U4") (pin "4") (pinfunction "NC_4") (pintype "input"))
    )
    (net (code "73") (name "unconnected-(U4-NC-Pad6)") (class "Default")
      (node (ref "U4") (pin "6") (pinfunction "NC_6") (pintype "bidirectional"))
    )
    (net (code "74") (name "unconnected-(U4-NC-Pad7)") (class "Default")
      (node (ref "U4") (pin "7") (pinfunction "NC_7") (pintype "input"))
    )
    (net (code "75") (name "unconnected-(U5-D0-PadA6)") (class "Default")
      (node (ref "U5") (pin "A6") (pinfunction "D0_A6") (pintype "bidirectional"))
    )
    (net (code "76") (name "unconnected-(U5-D1-PadE2)") (class "Default")
      (node (ref "U5") (pin "E2") (pinfunction "D1_E2") (pintype "bidirectional"))
    )
    (net (code "77") (name "unconnected-(U8-PA0{slash}USART2_CTS{slash}UART4_TX{slash}TIM2_CH1_ETR{slash}WKUP{slash}TIM5_CH1{slash}TIM8_ETR-Pad23)") (class "Default")
      (node (ref "U8") (pin "23") (pinfunction "PA0/USART2_CTS/UART4_TX/TIM2_CH1_ETR/WKUP/TIM5_CH1/TIM8_ETR_23") (pintype "bidirectional"))
    )
    (net (code "78") (name "unconnected-(U8-PA1{slash}USART2_RTS{slash}UART4_RX{slash}TIM5_CH2{slash}TIMM2_CH2{slash}EVENTOUT-Pad24)") (class "Default")
      (node (ref "U8") (pin "24") (pinfunction "PA1/USART2_RTS/UART4_RX/TIM5_CH2/TIMM2_CH2/EVENTOUT_24") (pintype "bidirectional"))
    )
    (net (code "79") (name "unconnected-(U8-PA2{slash}USART2_TX{slash}TIM5_CH3{slash}TIM9_CH1{slash}TIM2_CH3{slash}ETH_MDIO-Pad25)") (class "Default")
      (node (ref "U8") (pin "25") (pinfunction "PA2/USART2_TX/TIM5_CH3/TIM9_CH1/TIM2_CH3/ETH_MDIO_25") (pintype "bidirectional"))
    )
    (net (code "80") (name "unconnected-(U8-PA3{slash}USART2_RX{slash}TIM5_CH4{slash}TIM9_CH2{slash}TIM2_CH4{slash}OTG_HS_ULPI_D0-Pad26)") (class "Default")
      (node (ref "U8") (pin "26") (pinfunction "PA3/USART2_RX/TIM5_CH4/TIM9_CH2/TIM2_CH4/OTG_HS_ULPI_D0_26") (pintype "bidirectional"))
    )
    (net (code "81") (name "unconnected-(U8-PA7{slash}SPI1_MOSI{slash}TIM8_CH1N{slash}TIM14_CH1TIM3_CH2-Pad32)") (class "Default")
      (node (ref "U8") (pin "32") (pinfunction "PA7/SPI1_MOSI/TIM8_CH1N/TIM14_CH1TIM3_CH2_32") (pintype "bidirectional"))
    )
    (net (code "82") (name "unconnected-(U8-PB0{slash}TIM3_CH3{slash}TIM8_CH2N{slash}OTG_HS_ULPI_D1{slash}ETH_MII_RXD2{slash}TIM1_CH2N{slash}-Pad35)") (class "Default")
      (node (ref "U8") (pin "35") (pinfunction "PB0/TIM3_CH3/TIM8_CH2N/OTG_HS_ULPI_D1/ETH_MII_RXD2/TIM1_CH2N/_35") (pintype "bidirectional"))
    )
    (net (code "83") (name "unconnected-(U8-PB1{slash}TIM3_CH4{slash}TIM8_CH3N{slash}OTG_HS_ULPI_D2{slash}ETH_MII_RXD3{slash}OTG_HS_INTN{slash}-Pad36)") (class "Default")
      (node (ref "U8") (pin "36") (pinfunction "PB1/TIM3_CH4/TIM8_CH3N/OTG_HS_ULPI_D2/ETH_MII_RXD3/OTG_HS_INTN/_36") (pintype "bidirectional"))
    )
    (net (code "84") (name "unconnected-(U8-PB3{slash}JTDO{slash}TRACESWO{slash}SPI3_SCK{slash}I2S3_CK{slash}TIM2_CH2{slash}SPI1_SCK-Pad89)") (class "Default")
      (node (ref "U8") (pin "89") (pinfunction "PB3/JTDO/TRACESWO/SPI3_SCK/I2S3_CK/TIM2_CH2/SPI1_SCK_89") (pintype "bidirectional"))
    )
    (net (code "85") (name "unconnected-(U8-PB4{slash}NJTRST{slash}SPI3_MISO{slash}TIM3_CH1{slash}SPI1_MISO{slash}I2S3EXT_SD-Pad90)") (class "Default")
      (node (ref "U8") (pin "90") (pinfunction "PB4/NJTRST/SPI3_MISO/TIM3_CH1/SPI1_MISO/I2S3EXT_SD_90") (pintype "bidirectional"))
    )
    (net (code "86") (name "unconnected-(U8-PC3{slash}SPI2_MOSI{slash}I2S2_SD{slash}OTG_HS_ULPI_NXT{slash}ETH_MII_TX_CLK{slash}ADC123_IN13-Pad18)") (class "Default")
      (node (ref "U8") (pin "18") (pinfunction "PC3/SPI2_MOSI/I2S2_SD/OTG_HS_ULPI_NXT/ETH_MII_TX_CLK/ADC123_IN13_18") (pintype "bidirectional"))
    )
    (net (code "87") (name "unconnected-(U8-PC4{slash}ETH_RMII_RX_D0{slash}ETH_MII_RX_D0{slash}ADC12_IN14-Pad33)") (class "Default")
      (node (ref "U8") (pin "33") (pinfunction "PC4/ETH_RMII_RX_D0/ETH_MII_RX_D0/ADC12_IN14_33") (pintype "bidirectional"))
    )
    (net (code "88") (name "unconnected-(U8-PC5{slash}ETH_RMII_RX_D1{slash}ETH_MII_RX_D1{slash}ADC12_IN15-Pad34)") (class "Default")
      (node (ref "U8") (pin "34") (pinfunction "PC5/ETH_RMII_RX_D1/ETH_MII_RX_D1/ADC12_IN15_34") (pintype "bidirectional"))
    )
    (net (code "89") (name "unconnected-(U8-PC13{slash}RTC_AF1-Pad7)") (class "Default")
      (node (ref "U8") (pin "7") (pinfunction "PC13/RTC_AF1_7") (pintype "bidirectional"))
    )
    (net (code "90") (name "unconnected-(U8-PC14{slash}OSC32_IN-Pad8)") (class "Default")
      (node (ref "U8") (pin "8") (pinfunction "PC14/OSC32_IN_8") (pintype "bidirectional"))
    )
    (net (code "91") (name "unconnected-(U8-PC15{slash}OSC32_OUT-Pad9)") (class "Default")
      (node (ref "U8") (pin "9") (pinfunction "PC15/OSC32_OUT_9") (pintype "bidirectional"))
    )
    (net (code "92") (name "unconnected-(U8-PD0{slash}FSMC_D2{slash}CAN1_RX-Pad81)") (class "Default")
      (node (ref "U8") (pin "81") (pinfunction "PD0/FSMC_D2/CAN1_RX_81") (pintype "bidirectional"))
    )
    (net (code "93") (name "unconnected-(U8-PD1FSMC_D3{slash}CAN1_TX-Pad82)") (class "Default")
      (node (ref "U8") (pin "82") (pinfunction "PD1FSMC_D3/CAN1_TX_82") (pintype "bidirectional"))
    )
    (net (code "94") (name "unconnected-(U8-PD4{slash}FSMC_NOE{slash}USART2_RTS-Pad85)") (class "Default")
      (node (ref "U8") (pin "85") (pinfunction "PD4/FSMC_NOE/USART2_RTS_85") (pintype "bidirectional"))
    )
    (net (code "95") (name "unconnected-(U8-PD5{slash}FSMC_NWE{slash}USART2_TX-Pad86)") (class "Default")
      (node (ref "U8") (pin "86") (pinfunction "PD5/FSMC_NWE/USART2_TX_86") (pintype "bidirectional"))
    )
    (net (code "96") (name "unconnected-(U8-PD6{slash}FSMC_NWAIT{slash}USART2_RX-Pad87)") (class "Default")
      (node (ref "U8") (pin "87") (pinfunction "PD6/FSMC_NWAIT/USART2_RX_87") (pintype "bidirectional"))
    )
    (net (code "97") (name "unconnected-(U8-PD7{slash}USART2_CK{slash}FSMC_NE1{slash}FSMC_NCE2-Pad88)") (class "Default")
      (node (ref "U8") (pin "88") (pinfunction "PD7/USART2_CK/FSMC_NE1/FSMC_NCE2_88") (pintype "bidirectional"))
    )
    (net (code "98") (name "unconnected-(U8-PD10{slash}FSMC_D15{slash}USART3_CK-Pad57)") (class "Default")
      (node (ref "U8") (pin "57") (pinfunction "PD10/FSMC_D15/USART3_CK_57") (pintype "bidirectional"))
    )
    (net (code "99") (name "unconnected-(U8-PD11{slash}FSMC_A16{slash}USART3_CTS-Pad58)") (class "Default")
      (node (ref "U8") (pin "58") (pinfunction "PD11/FSMC_A16/USART3_CTS_58") (pintype "bidirectional"))
    )
    (net (code "100") (name "unconnected-(U8-PD14{slash}FSMC_D0{slash}TIM4_CH3-Pad61)") (class "Default")
      (node (ref "U8") (pin "61") (pinfunction "PD14/FSMC_D0/TIM4_CH3_61") (pintype "bidirectional"))
    )
    (net (code "101") (name "unconnected-(U8-PD15{slash}FSMC_D1{slash}TIM4_CH4-Pad62)") (class "Default")
      (node (ref "U8") (pin "62") (pinfunction "PD15/FSMC_D1/TIM4_CH4_62") (pintype "bidirectional"))
    )
    (net (code "102") (name "unconnected-(U8-PE3{slash}TRACED0{slash}FSMC_A19-Pad2)") (class "Default")
      (node (ref "U8") (pin "2") (pinfunction "PE3/TRACED0/FSMC_A19_2") (pintype "bidirectional"))
    )
    (net (code "103") (name "unconnected-(U8-PE7{slash}FSMC_D4{slash}TIM1_ETR-Pad38)") (class "Default")
      (node (ref "U8") (pin "38") (pinfunction "PE7/FSMC_D4/TIM1_ETR_38") (pintype "bidirectional"))
    )
    (net (code "104") (name "unconnected-(U8-PE8{slash}FSMC_D5{slash}TIM1_CH1N-Pad39)") (class "Default")
      (node (ref "U8") (pin "39") (pinfunction "PE8/FSMC_D5/TIM1_CH1N_39") (pintype "bidirectional"))
    )
    (net (code "105") (name "unconnected-(U8-PE9{slash}FSMC_D6{slash}TIM1_CH1-Pad40)") (class "Default")
      (node (ref "U8") (pin "40") (pinfunction "PE9/FSMC_D6/TIM1_CH1_40") (pintype "bidirectional"))
    )
    (net (code "106") (name "unconnected-(U8-PE10{slash}FSMC_D7{slash}TIM1_CH2N-Pad41)") (class "Default")
      (node (ref "U8") (pin "41") (pinfunction "PE10/FSMC_D7/TIM1_CH2N_41") (pintype "bidirectional"))
    )
    (net (code "107") (name "unconnected-(U8-PE11{slash}FSMC_D8{slash}TIM1_CH2-Pad42)") (class "Default")
      (node (ref "U8") (pin "42") (pinfunction "PE11/FSMC_D8/TIM1_CH2_42") (pintype "bidirectional"))
    )
    (net (code "108") (name "unconnected-(U8-PE12{slash}FSMC_D9{slash}TIM1_CH3N-Pad43)") (class "Default")
      (node (ref "U8") (pin "43") (pinfunction "PE12/FSMC_D9/TIM1_CH3N_43") (pintype "bidirectional"))
    )
    (net (code "109") (name "unconnected-(U8-PE13{slash}FSMC_D10{slash}TIM1_CH3-Pad44)") (class "Default")
      (node (ref "U8") (pin "44") (pinfunction "PE13/FSMC_D10/TIM1_CH3_44") (pintype "bidirectional"))
    )
    (net (code "110") (name "unconnected-(U8-PE14{slash}FSMC_D11{slash}TIM1_CH4-Pad45)") (class "Default")
      (node (ref "U8") (pin "45") (pinfunction "PE14/FSMC_D11/TIM1_CH4_45") (pintype "bidirectional"))
    )
    (net (code "111") (name "unconnected-(U8-PE15FSMC_D12{slash}TIM1_BKIN-Pad46)") (class "Default")
      (node (ref "U8") (pin "46") (pinfunction "PE15FSMC_D12/TIM1_BKIN_46") (pintype "bidirectional"))
    )
    (net (code "112") (name "unconnected-(X2-GND1-PadMT1)") (class "Default")
      (node (ref "X2") (pin "MT1") (pinfunction "GND1_MT1") (pintype "passive"))
    )
    (net (code "113") (name "unconnected-(X2-GND2-PadMT2)") (class "Default")
      (node (ref "X2") (pin "MT2") (pinfunction "GND2_MT2") (pintype "passive"))
    )
    (net (code "114") (name "unconnected-(X2-GND3-PadMT5)") (class "Default")
      (node (ref "X2") (pin "MT5") (pinfunction "GND3_MT5") (pintype "passive"))
    )
    (net (code "115") (name "unconnected-(X2-GND4-PadMT6)") (class "Default")
      (node (ref "X2") (pin "MT6") (pinfunction "GND4_MT6") (pintype "passive"))
    )
  )
)
